# SAMV71_Xplained_Ultra_Power_Supply.net
KiCad netlist of a schematic drawn in Altium Designer
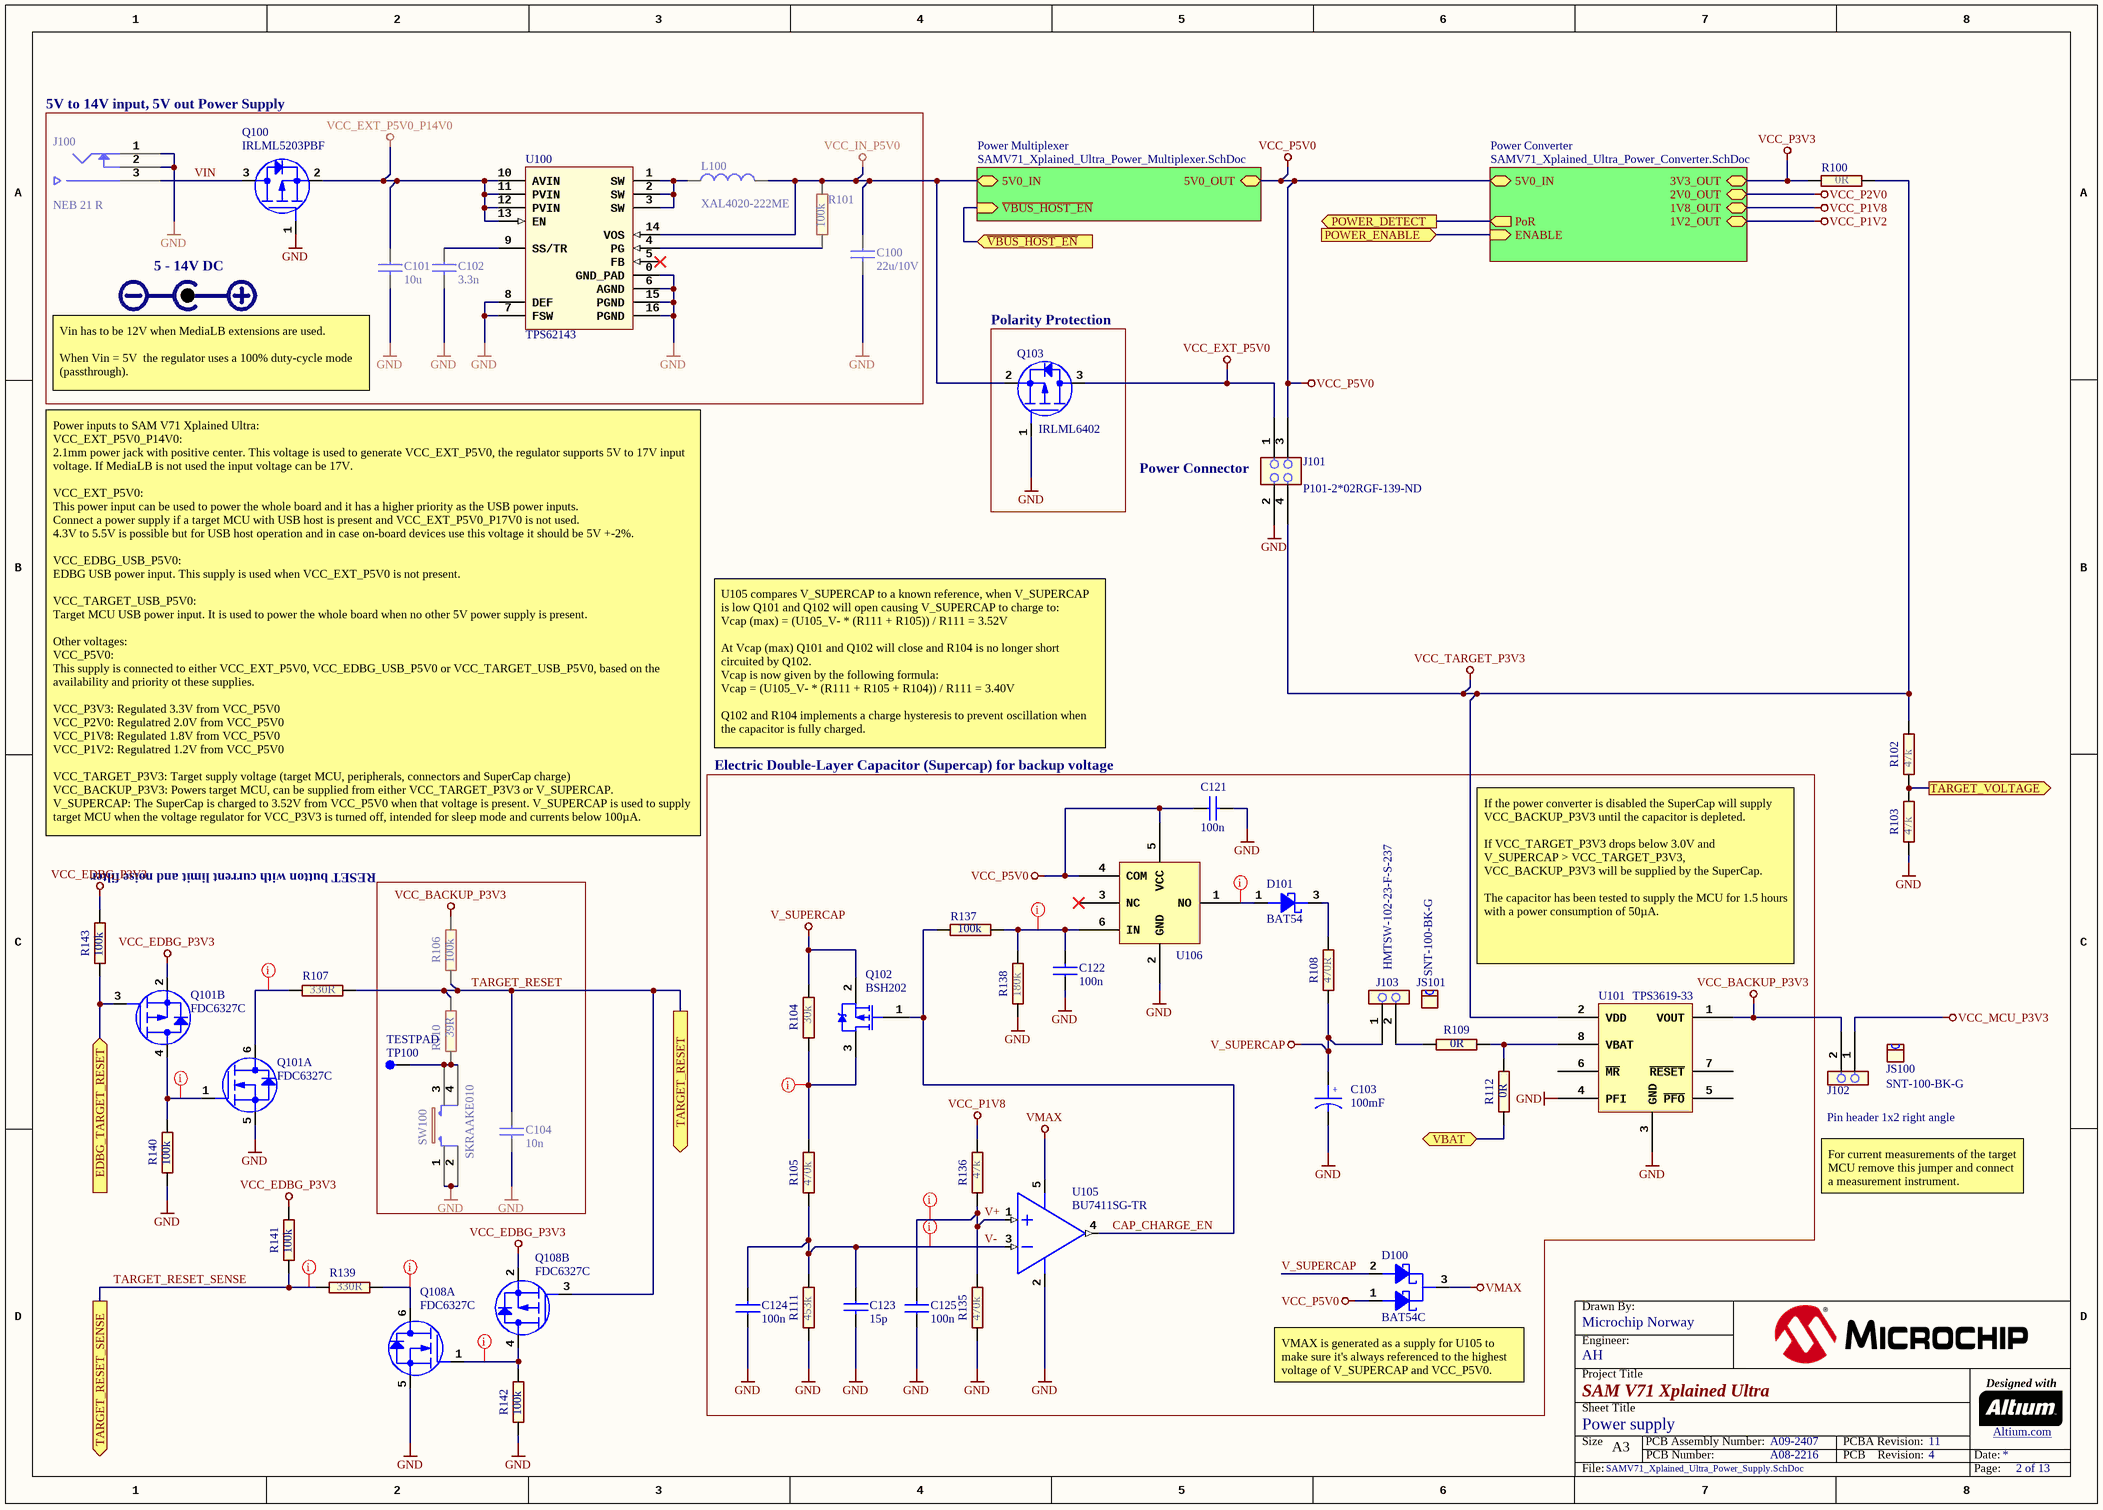
[diagram p0: SAMV71_Xplained_Ultra_Power_Supply.SchDoc]

(export (version "E")
  (design (tool "Eeschema 10.0.6"))
  (components
    (comp (ref "C100")
      (value "22u/10V")
      (footprint "AP1-00003")
      (description "Ceramic capacitor, SMD 0805, X5R, 10V, Â±20%")
      (fields (field (name "MANUFACTURER") "tdk") (field (name "MPN") "C2012X5R1A226M/0.85"))
      (libsource (lib "AltiumDbLib") (part "CAP-NONPOL"))
    )
    (comp (ref "C101")
      (value "10u")
      (footprint "AP1-00003")
      (description "Ceramic capacitor, SMD 0805, X5R, 25V, Â±10%")
      (fields (field (name "TOLERANCE") "Â±10%") (field (name "MANUFACTURER") "Murata"))
      (libsource (lib "AltiumDbLib") (part "CAP-NONPOL"))
    )
    (comp (ref "C102")
      (value "3.3n")
      (footprint "AP1-00001")
      (description "Ceramic capacitor, SMD 0402, X7R, 25V, +/-10%")
      (fields (field (name "TOLERANCE") "25V, +/-10%") (field (name "MANUFACTURER") "YAGEO CORP"))
      (libsource (lib "AltiumDbLib") (part "CAP-NONPOL"))
    )
    (comp (ref "C103")
      (value "100mF")
      (footprint "AP1-00122")
      (description "Electric Double-Layer (Supercapacitor), 100mF, SMD, 10.5mm diameter, 25Î© ESR")
      (fields (field (name "TOLERANCE") "-20/+80%") (field (name "MANUFACTURER") "Kemet"))
      (libsource (lib "AltiumDbLib") (part "CAP-POL"))
    )
    (comp (ref "C104")
      (value "10n")
      (footprint "AP1-00053")
      (description "Ceramic capacitor, SMD 0402, X7R, 25V, +/-10%")
      (fields (field (name "TOLERANCE") "25V, +/-10%") (field (name "MANUFACTURER") "YAGEO CORP"))
      (libsource (lib "AltiumDbLib") (part "CAP-NONPOL"))
    )
    (comp (ref "C121")
      (value "100n")
      (footprint "AP1-00001")
      (description "Ceramic capacitor, SMD 0402, X7R, 16V, +/-10%")
      (fields (field (name "TOLERANCE") "16V, +/-10%") (field (name "MANUFACTURER") "Kemet"))
      (libsource (lib "AltiumDbLib") (part "CAP-NONPOL"))
    )
    (comp (ref "C122")
      (value "100n")
      (footprint "AP1-00053")
      (description "Ceramic capacitor, SMD 0402, X7R, 16V, +/-10%")
      (fields (field (name "TOLERANCE") "16V, +/-10%") (field (name "MANUFACTURER") "Kemet"))
      (libsource (lib "AltiumDbLib") (part "CAP-NONPOL"))
    )
    (comp (ref "C123")
      (value "15p")
      (footprint "AP1-00001")
      (description "Ceramic capacitor, SMD 0402, NP0, 50V, +/-5%")
      (fields (field (name "TOLERANCE") "50V, +/-5%") (field (name "MANUFACTURER") "AVX"))
      (libsource (lib "AltiumDbLib") (part "CAP-NONPOL"))
    )
    (comp (ref "C124")
      (value "100n")
      (footprint "AP1-00001")
      (description "Ceramic capacitor, SMD 0402, X7R, 16V, +/-10%")
      (fields (field (name "TOLERANCE") "16V, +/-10%") (field (name "MANUFACTURER") "Kemet"))
      (libsource (lib "AltiumDbLib") (part "CAP-NONPOL"))
    )
    (comp (ref "C125")
      (value "100n")
      (footprint "AP1-00001")
      (description "Ceramic capacitor, SMD 0402, X7R, 16V, +/-10%")
      (fields (field (name "TOLERANCE") "16V, +/-10%") (field (name "MANUFACTURER") "Kemet"))
      (libsource (lib "AltiumDbLib") (part "CAP-NONPOL"))
    )
    (comp (ref "D100")
      (value "BAT54C")
      (footprint "AP5-00002")
      (description "Schottky double Diodes, NXP, SOT23-3")
      (fields (field (name "MANUFACTURER") "NXP"))
      (libsource (lib "AltiumDbLib") (part "DUAL_SCHOTTKY_123"))
    )
    (comp (ref "D101")
      (value "BAT54")
      (footprint "AP4-00007")
      (fields (field (name "MANUFACTURER") "Philips"))
      (libsource (lib "AltiumDbLib") (part "SCHOTTKY_SMD_31"))
    )
    (comp (ref "J100")
      (value "NEB 21 R")
      (footprint "AP8-00853")
      (description "Through hole DC jack 2.1mm, 12V, 3A")
      (fields (field (name "MANUFACTURER") "Lumberg"))
      (libsource (lib "AltiumDbLib") (part "DC_JACK"))
    )
    (comp (ref "J101")
      (value "P101-2*02RGF-139-ND")
      (footprint "AP8-00628")
      (description "Pin header, 2x2, Right Angle, 2.54mm, THT, Pin In Paste")
      (fields (field (name "MANUFACTURER") "Pro-data International Corp"))
      (libsource (lib "AltiumDbLib") (part "HEADER 2x2"))
    )
    (comp (ref "J102")
      (value "Pin header 1x2 right angle")
      (footprint "AP8-00367")
      (description "1x2 pin header, right angle, 2.54 mm pitch, through-hole")
      (fields (field (name "MANUFACTURER") "Pro-data International Corp") (field (name "MPN") "2213R-2G"))
      (libsource (lib "") (part "HEADER 1x2_1"))
    )
    (comp (ref "J103")
      (value "HMTSW-102-23-F-S-237")
      (footprint "AP8-00733")
      (description "1x2 pin header, 2.54mm pitch, Pin-in-Paste THM")
      (fields (field (name "MANUFACTURER") "SAMTEC"))
      (libsource (lib "AltiumDbLib") (part "HEADER 1x2"))
    )
    (comp (ref "JS100")
      (value "SNT-100-BK-G")
      (footprint "AP8-00525")
      (description "Jumper cap for 2.54mm pinheader")
      (fields (field (name "MANUFACTURER") "SAMTEC"))
      (libsource (lib "AltiumDbLib") (part "JUMPER_CAP"))
    )
    (comp (ref "JS101")
      (value "SNT-100-BK-G")
      (footprint "AP8-00525")
      (description "Jumper cap for 2.54mm pinheader")
      (fields (field (name "MANUFACTURER") "SAMTEC"))
      (libsource (lib "AltiumDbLib") (part "JUMPER_CAP"))
    )
    (comp (ref "L100")
      (value "XAL4020-222ME")
      (footprint "AP3-00119")
      (description "2.2ÂµH Shielded Power Inductor, 4x4x2mm, Isat=5.6A , Irms=4.0A , DCR=35.2mÎ©")
      (fields (field (name "TOLERANCE") "20%") (field (name "MANUFACTURER") "Coilcraft"))
      (libsource (lib "AltiumDbLib") (part "INDUCTOR"))
    )
    (comp (ref "Q100")
      (value "IRLML5203PBF")
      (footprint "AP5-00002")
      (fields (field (name "MANUFACTURER") "International Rectifier"))
      (libsource (lib "AltiumDbLib") (part "MOSFET_P_GSD"))
    )
    (comp (ref "Q101")
      (value "FDC6327C")
      (footprint "AP5-00008")
      (fields (field (name "MANUFACTURER") "Fairchild") (field (name "Comment") "Farnell no: 9844856"))
      (libsource (lib "AltiumDbLib") (part "DUAL_NP_G1S2G2D2S1D1"))
    )
    (comp (ref "Q102")
      (value "BSH202")
      (footprint "AP4-00018")
      (description "P-channel Power MOSFET,30V, 520mA continuous drain current")
      (fields (field (name "MANUFACTURER") "NXP"))
      (libsource (lib "AltiumDbLib") (part "BSH202"))
    )
    (comp (ref "Q103")
      (value "IRLML6402")
      (footprint "AP5-00002")
      (description "P-ch. MOSFET. -30V, -3.7A continuous,RDS(ON)=0.05Ohm@VGS=-4,5V, RDS(ON)=0.08Ohm@VGS=-2.5V")
      (fields (field (name "MANUFACTURER") "International Rectifier") (field (name "MPN") "IRLML6402PBF"))
      (libsource (lib "AltiumDbLib") (part "MOSFET_P_GSD"))
    )
    (comp (ref "Q108")
      (value "FDC6327C")
      (footprint "AP5-00008")
      (fields (field (name "MANUFACTURER") "Fairchild") (field (name "Comment") "Farnell no: 9844856"))
      (libsource (lib "AltiumDbLib") (part "DUAL_NP_G1S2G2D2S1D1"))
    )
    (comp (ref "R100")
      (value "0R")
      (footprint "AP2-00000")
      (description "Thick film resistor, SMD 0402, 1/16W, 1%")
      (fields (field (name "TOLERANCE") "1 %") (field (name "MANUFACTURER") "(n/a)"))
      (libsource (lib "") (part "R2_2"))
    )
    (comp (ref "R101")
      (value "100k")
      (footprint "AP2-00000")
      (description "Thick film resistor, SMD 0402, 1/16W, 1%")
      (fields (field (name "TOLERANCE") "1 %") (field (name "MANUFACTURER") "ASJ"))
      (libsource (lib "") (part "R2_3"))
    )
    (comp (ref "R102")
      (value "47k")
      (footprint "AP2-00000")
      (description "Thick film resistor, SMD 0402, 1/16W, 1%")
      (fields (field (name "TOLERANCE") "1 %") (field (name "MANUFACTURER") "KOA"))
      (libsource (lib "") (part "R2_1"))
    )
    (comp (ref "R103")
      (value "47k")
      (footprint "AP2-00000")
      (description "Thick film resistor, SMD 0402, 1/16W, 1%")
      (fields (field (name "TOLERANCE") "1 %") (field (name "MANUFACTURER") "KOA"))
      (libsource (lib "") (part "R2_1"))
    )
    (comp (ref "R104")
      (value "30k")
      (footprint "AP2-00000")
      (description "Thick film resistor, SMD 0402, 1/16W, 1%")
      (fields (field (name "TOLERANCE") "1 %") (field (name "MANUFACTURER") "ASJ"))
      (libsource (lib "AltiumDbLib") (part "R2"))
    )
    (comp (ref "R105")
      (value "470k")
      (footprint "AP2-00000")
      (description "Thick film resistor, SMD 0402, 1/16W, 1%")
      (fields (field (name "TOLERANCE") "1 %") (field (name "MANUFACTURER") "ASJ"))
      (libsource (lib "AltiumDbLib") (part "R2"))
    )
    (comp (ref "R106")
      (value "100k")
      (footprint "AP2-00011")
      (description "Thick film resistor, SMD 0402, 1/16W, 1%")
      (fields (field (name "TOLERANCE") "1 %") (field (name "MANUFACTURER") "ASJ"))
      (libsource (lib "AltiumDbLib") (part "R2"))
    )
    (comp (ref "R107")
      (value "330R")
      (footprint "AP2-00011")
      (description "Thick film resistor, SMD 0402, 1/16W, 1%")
      (fields (field (name "TOLERANCE") "1 %") (field (name "MANUFACTURER") "ASJ"))
      (libsource (lib "") (part "R2_2"))
    )
    (comp (ref "R108")
      (value "470R")
      (footprint "AP2-00000")
      (description "Thick film resistor, SMD 0402, 1/16W, 1%")
      (fields (field (name "TOLERANCE") "1 %") (field (name "MANUFACTURER") "ASJ"))
      (libsource (lib "") (part "R2_3"))
    )
    (comp (ref "R109")
      (value "0R")
      (footprint "AP2-00000")
      (description "RES 0.0 OHM 1/16W 0402 SMD")
      (fields (field (name "TOLERANCE") "1 %") (field (name "MANUFACTURER") "(n/a)"))
      (libsource (lib "") (part "R2_2"))
    )
    (comp (ref "R110")
      (value "39R")
      (footprint "AP2-00011")
      (description "Thick film resistor, SMD 0402, 1/16W, 1%")
      (fields (field (name "TOLERANCE") "1 %") (field (name "MANUFACTURER") "ASJ"))
      (libsource (lib "") (part "R2_4"))
    )
    (comp (ref "R111")
      (value "453k")
      (footprint "AP2-00000")
      (description "Thick film resistor, SMD 0402, 1/16W, 1%")
      (fields (field (name "TOLERANCE") "1 %"))
      (libsource (lib "AltiumDbLib") (part "R2"))
    )
    (comp (ref "R112")
      (value "0R")
      (footprint "AP2-00000")
      (description "RES 0.0 OHM 1/16W 0402 SMD")
      (fields (field (name "TOLERANCE") "1 %") (field (name "MANUFACTURER") "(n/a)"))
      (libsource (lib "AltiumDbLib") (part "R2"))
    )
    (comp (ref "R135")
      (value "470k")
      (footprint "AP2-00000")
      (description "Thick film resistor, SMD 0402, 1/16W, 1%")
      (fields (field (name "TOLERANCE") "1 %") (field (name "MANUFACTURER") "ASJ"))
      (libsource (lib "AltiumDbLib") (part "R2"))
    )
    (comp (ref "R136")
      (value "47k")
      (footprint "AP2-00000")
      (description "Thick film resistor, SMD 0402, 1/16W, 1%")
      (fields (field (name "TOLERANCE") "1 %") (field (name "MANUFACTURER") "KOA"))
      (libsource (lib "AltiumDbLib") (part "R2"))
    )
    (comp (ref "R137")
      (value "100k")
      (footprint "AP2-00011")
      (description "Thick film resistor, SMD 0402, 1/16W, 1%")
      (fields (field (name "TOLERANCE") "1 %") (field (name "MANUFACTURER") "ASJ"))
      (libsource (lib "") (part "R2_2"))
    )
    (comp (ref "R138")
      (value "180k")
      (footprint "AP2-00011")
      (description "Thick film resistor, SMD 0402, 1/16W, 1%")
      (fields (field (name "TOLERANCE") "1 %") (field (name "MANUFACTURER") "ASJ"))
      (libsource (lib "AltiumDbLib") (part "R2"))
    )
    (comp (ref "R139")
      (value "330R")
      (footprint "AP2-00011")
      (description "Thick film resistor, SMD 0402, 1/16W, 1%")
      (fields (field (name "TOLERANCE") "1 %") (field (name "MANUFACTURER") "ASJ"))
      (libsource (lib "") (part "R2_2"))
    )
    (comp (ref "R140")
      (value "100k")
      (footprint "AP2-00011")
      (description "Thick film resistor, SMD 0402, 1/16W, 1%")
      (fields (field (name "TOLERANCE") "1 %") (field (name "MANUFACTURER") "ASJ"))
      (libsource (lib "AltiumDbLib") (part "R2"))
    )
    (comp (ref "R141")
      (value "100k")
      (footprint "AP2-00011")
      (description "Thick film resistor, SMD 0402, 1/16W, 1%")
      (fields (field (name "TOLERANCE") "1 %") (field (name "MANUFACTURER") "ASJ"))
      (libsource (lib "AltiumDbLib") (part "R2"))
    )
    (comp (ref "R142")
      (value "100k")
      (footprint "AP2-00011")
      (description "Thick film resistor, SMD 0402, 1/16W, 1%")
      (fields (field (name "TOLERANCE") "1 %") (field (name "MANUFACTURER") "ASJ"))
      (libsource (lib "AltiumDbLib") (part "R2"))
    )
    (comp (ref "R143")
      (value "100k")
      (footprint "AP2-00011")
      (description "Thick film resistor, SMD 0402, 1/16W, 1%")
      (fields (field (name "TOLERANCE") "1 %") (field (name "MANUFACTURER") "ASJ"))
      (libsource (lib "AltiumDbLib") (part "R2"))
    )
    (comp (ref "SW100")
      (value "SKRAAKE010")
      (footprint "AP8-00137")
      (description "6.2x6.2 mm SMD tact switch, same as A08-0091 but less force is needed")
      (fields (field (name "MANUFACTURER") "ALPS"))
      (libsource (lib "AltiumDbLib") (part "PUSHBUTTON1"))
    )
    (comp (ref "TP100")
      (value "TESTPAD")
      (footprint "AP8-00010")
      (description "Single SMD testpad")
      (libsource (lib "AltiumDbLib") (part "TESTPOINT"))
    )
    (comp (ref "U100")
      (value "TPS62143")
      (footprint "AP6-00313")
      (description "5V to 17V in, 5V 2A out, Step-Down Converter")
      (fields (field (name "MANUFACTURER") "Texas Instruments") (field (name "MPN") "TPS62143RGTR"))
      (libsource (lib "AltiumDbLib") (part "TPS62143"))
    )
    (comp (ref "U101")
      (value "TPS3619-33")
      (footprint "AP6-00382")
      (description "Backup battery supervisors for RAM retention")
      (fields (field (name "MANUFACTURER") "Texas Instruments") (field (name "MPN") "TPS3619-33DGK"))
      (libsource (lib "AltiumDbLib") (part "TPS3619"))
    )
    (comp (ref "U105")
      (value "BU7411SG-TR")
      (footprint "AP6-00087")
      (description "Single, Low Voltage (1.6-5.5V), Low Power (0.35ÂµA), low cost")
      (fields (field (name "MANUFACTURER") "ROHM"))
      (libsource (lib "AltiumDbLib") (part "LMV321M5"))
    )
    (comp (ref "U106")
      (value "~")
      (footprint "AP6-00056")
      (description "1.65V to 5.5V SPDT Analog switch")
      (fields (field (name "MANUFACTURER") "Texas Instruments") (field (name "MPN") "TS5A3160DBVR"))
      (libsource (lib "AltiumDbLib") (part "TS5A3160"))
    )
  )
  (nets
    (net (code "1") (name "/CAP_CHARGE_EN") (class "Default")
      (node (ref "Q102") (pin "1") (pinfunction "G_1") (pintype "passive"))
      (node (ref "R137") (pin "1") (pinfunction "1_1") (pintype "passive"))
      (node (ref "U105") (pin "4") (pinfunction "OUT_4") (pintype "output"))
    )
    (net (code "2") (name "/EDBG_TARGET_RESET") (class "Default")
      (node (ref "Q101") (pin "3") (pinfunction "G_3") (pintype "passive"))
      (node (ref "R143") (pin "1") (pinfunction "1_1") (pintype "passive"))
    )
    (net (code "5") (name "/TARGET_RESET") (class "Default")
      (node (ref "C104") (pin "1") (pinfunction "1_1") (pintype "passive"))
      (node (ref "Q108") (pin "3") (pinfunction "G_3") (pintype "passive"))
      (node (ref "R106") (pin "1") (pinfunction "1_1") (pintype "passive"))
      (node (ref "R107") (pin "2") (pinfunction "2_2") (pintype "passive"))
      (node (ref "R110") (pin "2") (pinfunction "2_2") (pintype "passive"))
    )
    (net (code "6") (name "/TARGET_RESET_SENSE") (class "Default")
      (node (ref "R139") (pin "1") (pinfunction "1_1") (pintype "passive"))
      (node (ref "R141") (pin "1") (pinfunction "1_1") (pintype "passive"))
    )
    (net (code "7") (name "/TARGET_VOLTAGE") (class "Default")
      (node (ref "R102") (pin "1") (pinfunction "1_1") (pintype "passive"))
      (node (ref "R103") (pin "2") (pinfunction "2_2") (pintype "passive"))
    )
    (net (code "8") (name "/V+") (class "Default")
      (node (ref "C125") (pin "2") (pinfunction "2_2") (pintype "passive"))
      (node (ref "R135") (pin "2") (pinfunction "2_2") (pintype "passive"))
      (node (ref "R136") (pin "1") (pinfunction "1_1") (pintype "passive"))
      (node (ref "U105") (pin "1") (pinfunction "IN+_1") (pintype "input"))
    )
    (net (code "9") (name "/V-") (class "Default")
      (node (ref "C123") (pin "1") (pinfunction "1_1") (pintype "passive"))
      (node (ref "C124") (pin "2") (pinfunction "2_2") (pintype "passive"))
      (node (ref "R105") (pin "1") (pinfunction "1_1") (pintype "passive"))
      (node (ref "R111") (pin "2") (pinfunction "2_2") (pintype "passive"))
      (node (ref "U105") (pin "3") (pinfunction "IN-_3") (pintype "input"))
    )
    (net (code "10") (name "/VBAT") (class "Default")
      (node (ref "R112") (pin "1") (pinfunction "1_1") (pintype "passive"))
    )
    (net (code "11") (name "/VIN") (class "Default")
      (node (ref "J100") (pin "3") (pinfunction "3_3") (pintype "passive"))
      (node (ref "Q100") (pin "3") (pinfunction "D_3") (pintype "passive"))
    )
    (net (code "13") (name "GND") (class "Default")
      (node (ref "C100") (pin "2") (pinfunction "2_2") (pintype "passive"))
      (node (ref "C101") (pin "2") (pinfunction "2_2") (pintype "passive"))
      (node (ref "C102") (pin "2") (pinfunction "2_2") (pintype "passive"))
      (node (ref "C103") (pin "2") (pinfunction "2_2") (pintype "passive"))
      (node (ref "C104") (pin "2") (pinfunction "2_2") (pintype "passive"))
      (node (ref "C121") (pin "2") (pinfunction "2_2") (pintype "passive"))
      (node (ref "C122") (pin "1") (pinfunction "1_1") (pintype "passive"))
      (node (ref "C123") (pin "2") (pinfunction "2_2") (pintype "passive"))
      (node (ref "C124") (pin "1") (pinfunction "1_1") (pintype "passive"))
      (node (ref "C125") (pin "1") (pinfunction "1_1") (pintype "passive"))
      (node (ref "J100") (pin "1") (pinfunction "1_1") (pintype "passive"))
      (node (ref "J100") (pin "2") (pinfunction "2_2") (pintype "passive"))
      (node (ref "J101") (pin "2") (pinfunction "2_2") (pintype "passive"))
      (node (ref "Q100") (pin "1") (pinfunction "G_1") (pintype "passive"))
      (node (ref "Q101") (pin "5") (pinfunction "S_5") (pintype "passive"))
      (node (ref "Q103") (pin "1") (pinfunction "G_1") (pintype "passive"))
      (node (ref "Q108") (pin "5") (pinfunction "S_5") (pintype "passive"))
      (node (ref "R103") (pin "1") (pinfunction "1_1") (pintype "passive"))
      (node (ref "R111") (pin "1") (pinfunction "1_1") (pintype "passive"))
      (node (ref "R135") (pin "1") (pinfunction "1_1") (pintype "passive"))
      (node (ref "R138") (pin "1") (pinfunction "1_1") (pintype "passive"))
      (node (ref "R140") (pin "1") (pinfunction "1_1") (pintype "passive"))
      (node (ref "R142") (pin "1") (pinfunction "1_1") (pintype "passive"))
      (node (ref "SW100") (pin "1") (pinfunction "1_1") (pintype "passive"))
      (node (ref "SW100") (pin "2") (pinfunction "2_2") (pintype "passive"))
      (node (ref "U100") (pin "0") (pinfunction "GND_PAD_0") (pintype "passive"))
      (node (ref "U100") (pin "15") (pinfunction "PGND_15") (pintype "power_in"))
      (node (ref "U100") (pin "16") (pinfunction "PGND_16") (pintype "power_in"))
      (node (ref "U100") (pin "6") (pinfunction "AGND_6") (pintype "power_in"))
      (node (ref "U100") (pin "7") (pinfunction "FSW_7") (pintype "power_in"))
      (node (ref "U100") (pin "8") (pinfunction "DEF_8") (pintype "power_in"))
      (node (ref "U101") (pin "3") (pinfunction "GND_3") (pintype "passive"))
      (node (ref "U101") (pin "4") (pinfunction "PFI_4") (pintype "passive"))
      (node (ref "U105") (pin "2") (pinfunction "GND_2") (pintype "power_in"))
      (node (ref "U106") (pin "2") (pinfunction "GND_2") (pintype "passive"))
    )
    (net (code "14") (name "Net-(D101-ANODE)") (class "Default")
      (node (ref "D101") (pin "1") (pinfunction "ANODE_1") (pintype "passive"))
      (node (ref "U106") (pin "1") (pinfunction "NO_1") (pintype "passive"))
    )
    (net (code "15") (name "Net-(D101-CATHODE)") (class "Default")
      (node (ref "D101") (pin "3") (pinfunction "CATHODE_3") (pintype "passive"))
      (node (ref "R108") (pin "1") (pinfunction "1_1") (pintype "passive"))
    )
    (net (code "16") (name "Net-(J103-Pad2)") (class "Default")
      (node (ref "J103") (pin "2") (pinfunction "2_2") (pintype "passive"))
      (node (ref "R109") (pin "1") (pinfunction "1_1") (pintype "passive"))
    )
    (net (code "17") (name "Net-(L100-Pad1)") (class "Default")
      (node (ref "L100") (pin "1") (pinfunction "1_1") (pintype "passive"))
      (node (ref "U100") (pin "1") (pinfunction "SW_1") (pintype "power_in"))
      (node (ref "U100") (pin "2") (pinfunction "SW_2") (pintype "power_in"))
      (node (ref "U100") (pin "3") (pinfunction "SW_3") (pintype "power_in"))
    )
    (net (code "18") (name "Net-(Q101A-D)") (class "Default")
      (node (ref "Q101") (pin "6") (pinfunction "D_6") (pintype "passive"))
      (node (ref "R107") (pin "1") (pinfunction "1_1") (pintype "passive"))
    )
    (net (code "19") (name "Net-(Q101A-G)") (class "Default")
      (node (ref "Q101") (pin "1") (pinfunction "G_1") (pintype "passive"))
      (node (ref "Q101") (pin "4") (pinfunction "D_4") (pintype "passive"))
      (node (ref "R140") (pin "2") (pinfunction "2_2") (pintype "passive"))
    )
    (net (code "20") (name "Net-(Q102-D)") (class "Default")
      (node (ref "Q102") (pin "3") (pinfunction "D_3") (pintype "passive"))
      (node (ref "R104") (pin "1") (pinfunction "1_1") (pintype "passive"))
      (node (ref "R105") (pin "2") (pinfunction "2_2") (pintype "passive"))
    )
    (net (code "21") (name "Net-(Q108A-D)") (class "Default")
      (node (ref "Q108") (pin "6") (pinfunction "D_6") (pintype "passive"))
      (node (ref "R139") (pin "2") (pinfunction "2_2") (pintype "passive"))
    )
    (net (code "22") (name "Net-(Q108A-G)") (class "Default")
      (node (ref "Q108") (pin "1") (pinfunction "G_1") (pintype "passive"))
      (node (ref "Q108") (pin "4") (pinfunction "D_4") (pintype "passive"))
      (node (ref "R142") (pin "2") (pinfunction "2_2") (pintype "passive"))
    )
    (net (code "23") (name "Net-(R110-Pad1)") (class "Default")
      (node (ref "R110") (pin "1") (pinfunction "1_1") (pintype "passive"))
      (node (ref "SW100") (pin "3") (pinfunction "3_3") (pintype "passive"))
      (node (ref "SW100") (pin "4") (pinfunction "4_4") (pintype "passive"))
      (node (ref "TP100") (pin "1") (pinfunction "1_1") (pintype "passive"))
    )
    (net (code "24") (name "Net-(U100-PG)") (class "Default")
      (node (ref "R101") (pin "2") (pinfunction "2_2") (pintype "passive"))
      (node (ref "U100") (pin "4") (pinfunction "PG_4") (pintype "input"))
    )
    (net (code "25") (name "Net-(U100-SS{slash}TR)") (class "Default")
      (node (ref "C102") (pin "1") (pinfunction "1_1") (pintype "passive"))
      (node (ref "U100") (pin "9") (pinfunction "SS/TR_9") (pintype "passive"))
    )
    (net (code "26") (name "Net-(U101-VBAT)") (class "Default")
      (node (ref "R109") (pin "2") (pinfunction "2_2") (pintype "passive"))
      (node (ref "R112") (pin "2") (pinfunction "2_2") (pintype "passive"))
      (node (ref "U101") (pin "8") (pinfunction "VBAT_8") (pintype "passive"))
    )
    (net (code "27") (name "Net-(U106-IN)") (class "Default")
      (node (ref "C122") (pin "2") (pinfunction "2_2") (pintype "passive"))
      (node (ref "R137") (pin "2") (pinfunction "2_2") (pintype "passive"))
      (node (ref "R138") (pin "2") (pinfunction "2_2") (pintype "passive"))
      (node (ref "U106") (pin "6") (pinfunction "IN_6") (pintype "passive"))
    )
    (net (code "28") (name "VCC_BACKUP_P3V3") (class "Default")
      (node (ref "J102") (pin "2") (pinfunction "2_2") (pintype "passive"))
      (node (ref "R106") (pin "2") (pinfunction "2_2") (pintype "passive"))
      (node (ref "U101") (pin "1") (pinfunction "VOUT_1") (pintype "passive"))
    )
    (net (code "29") (name "VCC_EDBG_P3V3") (class "Default")
      (node (ref "Q101") (pin "2") (pinfunction "S_2") (pintype "passive"))
      (node (ref "Q108") (pin "2") (pinfunction "S_2") (pintype "passive"))
      (node (ref "R141") (pin "2") (pinfunction "2_2") (pintype "passive"))
      (node (ref "R143") (pin "2") (pinfunction "2_2") (pintype "passive"))
    )
    (net (code "30") (name "VCC_EXT_P5V0") (class "Default")
      (node (ref "J101") (pin "1") (pinfunction "1_1") (pintype "passive"))
      (node (ref "Q103") (pin "3") (pinfunction "D_3") (pintype "passive"))
    )
    (net (code "31") (name "VCC_EXT_P5V0_P14V0") (class "Default")
      (node (ref "C101") (pin "1") (pinfunction "1_1") (pintype "passive"))
      (node (ref "Q100") (pin "2") (pinfunction "S_2") (pintype "passive"))
      (node (ref "U100") (pin "10") (pinfunction "AVIN_10") (pintype "power_in"))
      (node (ref "U100") (pin "11") (pinfunction "PVIN_11") (pintype "power_in"))
      (node (ref "U100") (pin "12") (pinfunction "PVIN_12") (pintype "power_in"))
      (node (ref "U100") (pin "13") (pinfunction "EN_13") (pintype "input"))
    )
    (net (code "32") (name "VCC_IN_P5V0") (class "Default")
      (node (ref "C100") (pin "1") (pinfunction "1_1") (pintype "passive"))
      (node (ref "L100") (pin "2") (pinfunction "2_2") (pintype "passive"))
      (node (ref "Q103") (pin "2") (pinfunction "S_2") (pintype "passive"))
      (node (ref "R101") (pin "1") (pinfunction "1_1") (pintype "passive"))
      (node (ref "U100") (pin "14") (pinfunction "VOS_14") (pintype "input"))
    )
    (net (code "33") (name "VCC_MCU_P3V3") (class "Default")
      (node (ref "J102") (pin "1") (pinfunction "1_1") (pintype "passive"))
    )
    (net (code "35") (name "VCC_P1V8") (class "Default")
      (node (ref "R136") (pin "2") (pinfunction "2_2") (pintype "passive"))
    )
    (net (code "37") (name "VCC_P3V3") (class "Default")
      (node (ref "R100") (pin "1") (pinfunction "1_1") (pintype "passive"))
    )
    (net (code "38") (name "VCC_P5V0") (class "Default")
      (node (ref "C121") (pin "1") (pinfunction "1_1") (pintype "passive"))
      (node (ref "D100") (pin "1") (pinfunction "ANODE1_1") (pintype "passive"))
      (node (ref "J101") (pin "3") (pinfunction "3_3") (pintype "passive"))
      (node (ref "U106") (pin "4") (pinfunction "COM_4") (pintype "passive"))
      (node (ref "U106") (pin "5") (pinfunction "VCC_5") (pintype "passive"))
    )
    (net (code "39") (name "VCC_TARGET_P3V3") (class "Default")
      (node (ref "J101") (pin "4") (pinfunction "4_4") (pintype "passive"))
      (node (ref "R100") (pin "2") (pinfunction "2_2") (pintype "passive"))
      (node (ref "R102") (pin "2") (pinfunction "2_2") (pintype "passive"))
      (node (ref "U101") (pin "2") (pinfunction "VDD_2") (pintype "passive"))
    )
    (net (code "40") (name "VMAX") (class "Default")
      (node (ref "D100") (pin "3") (pinfunction "CATHODE_3") (pintype "passive"))
      (node (ref "U105") (pin "5") (pinfunction "VCC_5") (pintype "power_in"))
    )
    (net (code "41") (name "V_SUPERCAP") (class "Default")
      (node (ref "C103") (pin "1") (pinfunction "1_1") (pintype "passive"))
      (node (ref "D100") (pin "2") (pinfunction "ANODE2_2") (pintype "passive"))
      (node (ref "J103") (pin "1") (pinfunction "1_1") (pintype "passive"))
      (node (ref "Q102") (pin "2") (pinfunction "S_2") (pintype "passive"))
      (node (ref "R104") (pin "2") (pinfunction "2_2") (pintype "passive"))
      (node (ref "R108") (pin "2") (pinfunction "2_2") (pintype "passive"))
    )
    (net (code "42") (name "unconnected-(U100-FB-Pad5)") (class "Default")
      (node (ref "U100") (pin "5") (pinfunction "FB_5") (pintype "input+no_connect"))
    )
    (net (code "43") (name "unconnected-(U101-~{MR}-Pad6)") (class "Default")
      (node (ref "U101") (pin "6") (pinfunction "~{MR}_6") (pintype "passive"))
    )
    (net (code "44") (name "unconnected-(U101-~{PFO}-Pad5)") (class "Default")
      (node (ref "U101") (pin "5") (pinfunction "~{PFO}_5") (pintype "passive"))
    )
    (net (code "45") (name "unconnected-(U101-~{RESET}-Pad7)") (class "Default")
      (node (ref "U101") (pin "7") (pinfunction "~{RESET}_7") (pintype "passive"))
    )
    (net (code "46") (name "unconnected-(U106-NC-Pad3)") (class "Default")
      (node (ref "U106") (pin "3") (pinfunction "NC_3") (pintype "passive+no_connect"))
    )
  )
)
